# CAN.net
KiCad netlist of a schematic drawn in Altium Designer
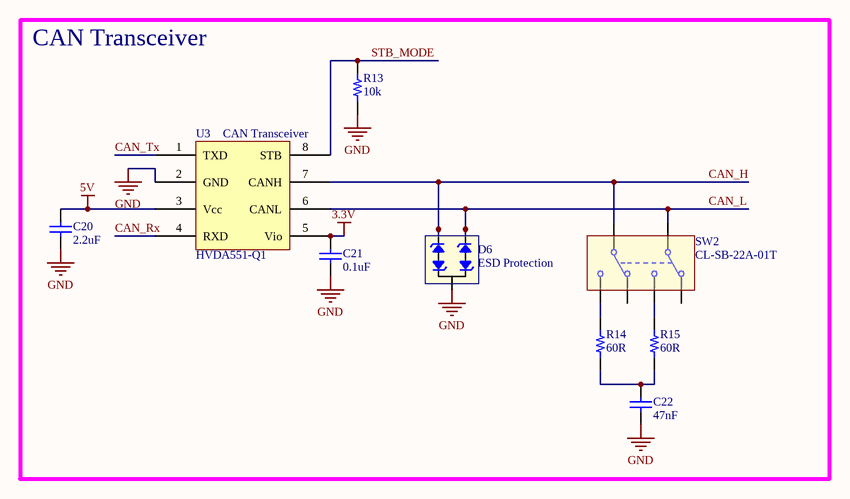
[diagram p0: CAN.SchDoc]

(export (version "E")
  (design (tool "Eeschema 10.0.6"))
  (components
    (comp (ref "C20")
      (value "2.2uF")
      (footprint "Capacitors:C0603")
      (description "2.2uF ceramic capacitor")
      (fields (field (name "MANUFACTURER") "TDK Corporation") (field (name "TOLERANCE") "10%"))
      (libsource (lib "Capacitors") (part "CAP CER 0603 2.2uF 6.3V X7R 10%"))
    )
    (comp (ref "C21")
      (value "0.1uF")
      (footprint "Capacitors:C0603")
      (description "0.1uF ceramic capacitor")
      (fields
        (field (name "MANUFACTURER") "Murata Electronics North America")
        (field (name "TOLERANCE") "10%")
      )
      (libsource (lib "Capacitors") (part "CAP CER 0603 0.1uF 50V C0G 10%"))
    )
    (comp (ref "C22")
      (value "47nF")
      (footprint "Capacitors:C0603")
      (description "47nF ceramic capacitor")
      (fields
        (field (name "MANUFACTURER") "Murata Electronics North America")
        (field (name "TOLERANCE") "10%")
      )
      (libsource (lib "Capacitors") (part "CAP CER 0603 47nF 50V X7R 10%"))
    )
    (comp (ref "D6")
      (value "ESD Protection")
      (footprint "SOT323")
      (description "CAN bus ESD protection diode")
      (fields (field (name "MANUFACTURER") "NXP") (field (name "PART_NUMBER") "PESD1CAN-UX"))
      (libsource (lib "Diodes") (part "PESD1CAN-UX"))
    )
    (comp (ref "R13")
      (value "10k")
      (footprint "R0603")
      (description "10 kOhms 1% 0.1W Resistor")
      (fields (field (name "MANUFACTURER") "Panasonic Electronic Components") (field (name "POWER") "0.1W"))
      (libsource (lib "Resistors") (part "RES 0603 10k 1% 0.1W"))
    )
    (comp (ref "R14")
      (value "60R")
      (footprint "R0603")
      (description "60 Ohms 0.25W Resistor")
      (fields (field (name "PART_NUMBER") "ESR03EZPJ620") (field (name "MANUFACTURER") "Rohm Semiconductor"))
      (libsource (lib "Resistors") (part "RES 0603 60R 1% 0.25W"))
    )
    (comp (ref "R15")
      (value "60R")
      (footprint "R0603")
      (description "60 Ohms 0.25W Resistor")
      (fields (field (name "PART_NUMBER") "ESR03EZPJ620") (field (name "MANUFACTURER") "Rohm Semiconductor"))
      (libsource (lib "Resistors") (part "RES 0603 60R 1% 0.25W"))
    )
    (comp (ref "SW2")
      (value "CL-SB-22A-01T")
      (footprint "CL-SB-22A-01T")
      (description "SWITCH SLIDE DPDT 200MA 12VDC")
      (fields
        (field (name "MANUFACTURER") "Copal Electronics Inc.")
        (field (name "PART_NUMBER") "CL-SB-22A-01T")
      )
      (libsource (lib "Other") (part "CL-SB-22A-01T"))
    )
    (comp (ref "U3")
      (value "CAN Transceiver")
      (footprint "SOIC-8")
      (description "Automotive 5-V CAN Transceiver with I/O Level Adapting and Low-Power Mode Supply Optimization")
      (fields (field (name "MANUFACTURER") "Texas Instrument") (field (name "PART_NUMBER") "HVDA551-Q1"))
      (libsource (lib "IC") (part "HVDA551-Q1"))
    )
  )
  (nets
    (net (code "1") (name "/CAN_H") (class "Default")
      (node (ref "D6") (pin "2") (pinfunction "2_2") (pintype "passive"))
      (node (ref "SW2") (pin "5") (pinfunction "COMMON2_5") (pintype "passive"))
      (node (ref "U3") (pin "7") (pinfunction "CANH_7") (pintype "passive"))
    )
    (net (code "2") (name "/CAN_L") (class "Default")
      (node (ref "D6") (pin "1") (pinfunction "1_1") (pintype "passive"))
      (node (ref "SW2") (pin "2") (pinfunction "COMMON1_2") (pintype "passive"))
      (node (ref "U3") (pin "6") (pinfunction "CANL_6") (pintype "passive"))
    )
    (net (code "3") (name "/CAN_Rx") (class "Default")
      (node (ref "U3") (pin "4") (pinfunction "RXD_4") (pintype "passive"))
    )
    (net (code "4") (name "/CAN_Tx") (class "Default")
      (node (ref "U3") (pin "1") (pinfunction "TXD_1") (pintype "passive"))
    )
    (net (code "5") (name "/STB_MODE") (class "Default")
      (node (ref "R13") (pin "2") (pinfunction "2_2") (pintype "passive"))
      (node (ref "U3") (pin "8") (pinfunction "STB_8") (pintype "passive"))
    )
    (net (code "6") (name "3.3V") (class "Default")
      (node (ref "C21") (pin "2") (pinfunction "2_2") (pintype "passive"))
      (node (ref "U3") (pin "5") (pinfunction "Vio_5") (pintype "passive"))
    )
    (net (code "7") (name "5V") (class "Default")
      (node (ref "C20") (pin "2") (pinfunction "2_2") (pintype "passive"))
      (node (ref "U3") (pin "3") (pinfunction "Vcc_3") (pintype "power_in"))
    )
    (net (code "8") (name "GND") (class "Default")
      (node (ref "C20") (pin "1") (pinfunction "1_1") (pintype "passive"))
      (node (ref "C21") (pin "1") (pinfunction "1_1") (pintype "passive"))
      (node (ref "C22") (pin "2") (pinfunction "2_2") (pintype "passive"))
      (node (ref "D6") (pin "3") (pinfunction "3_3") (pintype "passive"))
      (node (ref "R13") (pin "1") (pinfunction "1_1") (pintype "passive"))
      (node (ref "U3") (pin "2") (pinfunction "GND_2") (pintype "power_in"))
    )
    (net (code "9") (name "Net-(C22-Pad1)") (class "Default")
      (node (ref "C22") (pin "1") (pinfunction "1_1") (pintype "passive"))
      (node (ref "R14") (pin "1") (pinfunction "1_1") (pintype "passive"))
      (node (ref "R15") (pin "1") (pinfunction "1_1") (pintype "passive"))
    )
    (net (code "10") (name "Net-(SW2-NO1)") (class "Default")
      (node (ref "R15") (pin "2") (pinfunction "2_2") (pintype "passive"))
      (node (ref "SW2") (pin "3") (pinfunction "NO1_3") (pintype "passive"))
    )
    (net (code "11") (name "Net-(SW2-NO2)") (class "Default")
      (node (ref "R14") (pin "2") (pinfunction "2_2") (pintype "passive"))
      (node (ref "SW2") (pin "6") (pinfunction "NO2_6") (pintype "passive"))
    )
    (net (code "12") (name "unconnected-(SW2-NC1-Pad1)") (class "Default")
      (node (ref "SW2") (pin "1") (pinfunction "NC1_1") (pintype "passive"))
    )
    (net (code "13") (name "unconnected-(SW2-NC2-Pad4)") (class "Default")
      (node (ref "SW2") (pin "4") (pinfunction "NC2_4") (pintype "passive"))
    )
  )
)
